# Battery_Connections.net
KiCad netlist of a schematic drawn in Altium Designer
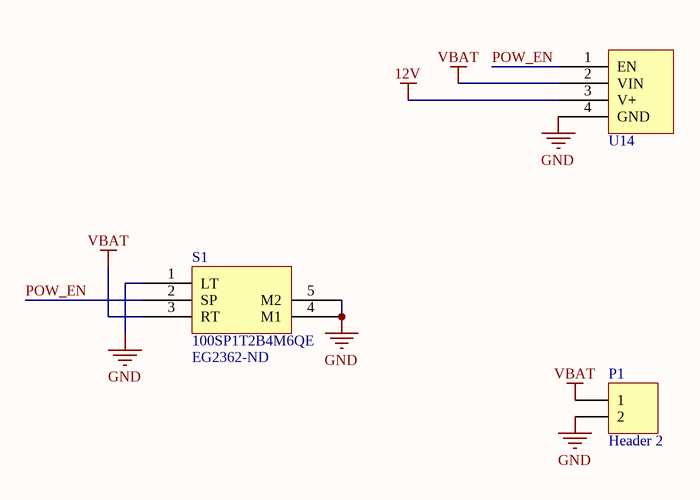
[diagram p0: Battery_Connections.SchDoc]

(export (version "E")
  (design (tool "Eeschema 10.0.6"))
  (components
    (comp (ref "P1")
      (value "Header 2")
      (footprint "HDR1X2")
      (description "Header, 2-Pin")
      (fields (field (name "PUBLISHER") "Altium Limited"))
      (libsource (lib "Miscellaneous Connectors") (part "Header 2"))
    )
    (comp (ref "S1")
      (value "100SP1T2B4M6QE")
      (footprint "100SP1T2B4M6QE")
      (fields (field (name "SUPPLIER PART NUMBER 1") "EG2362-ND"))
      (libsource (lib "Brain_Stim_Lib") (part "100SP1T2B4M6QE"))
    )
    (comp (ref "U14")
      (value "Adafruit 12V Bias Voltage Boost Converter - TPS61040")
      (footprint "12V_Suppy")
      (libsource (lib "Brain_Stim_Lib") (part "12V_Supply"))
    )
  )
  (nets
    (net (code "1") (name "/POW_EN") (class "Default")
      (node (ref "S1") (pin "2") (pinfunction "SP_2") (pintype "passive"))
      (node (ref "U14") (pin "1") (pinfunction "EN_1") (pintype "passive"))
    )
    (net (code "2") (name "12V") (class "Default")
      (node (ref "U14") (pin "3") (pinfunction "V+_3") (pintype "passive"))
    )
    (net (code "3") (name "GND") (class "Default")
      (node (ref "P1") (pin "2") (pinfunction "2_2") (pintype "passive"))
      (node (ref "S1") (pin "1") (pinfunction "LT_1") (pintype "passive"))
      (node (ref "S1") (pin "4") (pinfunction "M1_4") (pintype "passive"))
      (node (ref "S1") (pin "5") (pinfunction "M2_5") (pintype "passive"))
      (node (ref "U14") (pin "4") (pinfunction "GND_4") (pintype "passive"))
    )
    (net (code "4") (name "VBAT") (class "Default")
      (node (ref "P1") (pin "1") (pinfunction "1_1") (pintype "passive"))
      (node (ref "S1") (pin "3") (pinfunction "RT_3") (pintype "passive"))
      (node (ref "U14") (pin "2") (pinfunction "VIN_2") (pintype "passive"))
    )
  )
)
